# Sheet1.net
KiCad netlist of a schematic drawn in Altium Designer
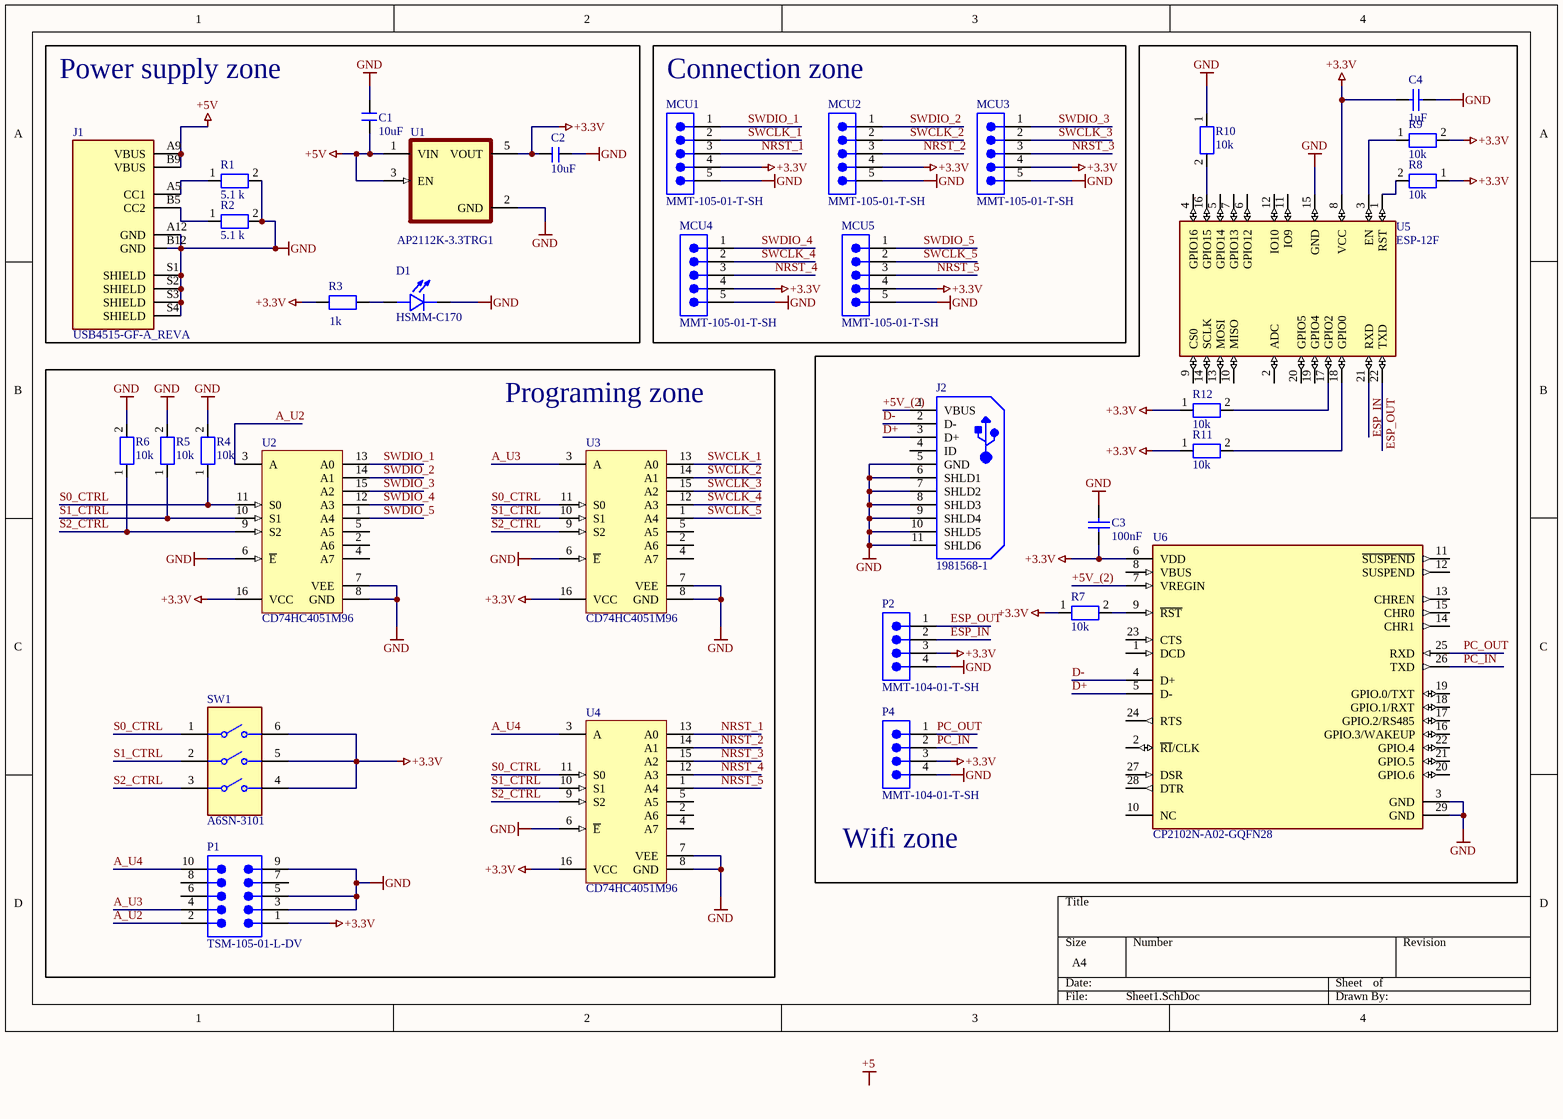
[diagram p0: Sheet1.SchDoc]

(export (version "E")
  (design (tool "Eeschema 10.0.6"))
  (components
    (comp (ref "C1")
      (value "10uF")
      (footprint "CAPC2012X145N")
      (description "10 ÂµF Â±10% 25V Ceramic Capacitor X5R 0805 (2012 Metric)")
      (fields (field (name "MF") "Samsung") (field (name "MP") "CL21A106KAYNNNE"))
      (libsource (lib "CL21A106KAYNNNE") (part "CL21A106KAYNNNE"))
    )
    (comp (ref "C2")
      (value "10uF")
      (footprint "CAPC2012X145N")
      (description "10 ÂµF Â±10% 25V Ceramic Capacitor X5R 0805 (2012 Metric)")
      (fields (field (name "MF") "Samsung") (field (name "MP") "CL21A106KAYNNNE"))
      (libsource (lib "CL21A106KAYNNNE") (part "CL21A106KAYNNNE"))
    )
    (comp (ref "C3")
      (value "100nF")
      (footprint "CAPC2013X135X50LL15T20")
      (fields (field (name "MANUFACTURER") "Vitramon") (field (name "PART NUMBER") "VJ0805Y104KXJCW1BC"))
      (libsource (lib "Altium Content Vault") (part "CAP"))
    )
    (comp (ref "C4")
      (value "1uF")
      (footprint "CAPC2013X140X50NL20T25")
      (fields
        (field (name "PART NUMBER") "0805YD105MAT2A")
        (field (name "MANUFACTURER") "AVX Interconnect / Elco")
      )
      (libsource (lib "Altium Content Vault") (part "CAP"))
    )
    (comp (ref "D1")
      (value "HSMM-C170")
      (footprint "LED_HSMM-C170")
      (libsource (lib "HSMM-C170") (part "HSMM-C170"))
    )
    (comp (ref "J1")
      (value "USB4515-GF-A_REVA")
      (footprint "GCT_USB4515-GF-A_REVA")
      (description "Type C USB Charging Connector")
      (fields
        (field (name "MF") "Global Connector Technology")
        (field (name "DIGI-KEY_PART_NUMBER") "2073-USB4515-GF-ATR-ND")
      )
      (libsource (lib "USB4515-GF-A_REVA") (part "USB4515-GF-A_REVA"))
    )
    (comp (ref "J2")
      (value "1981568-1")
      (footprint "TECO-1981568-5_V")
      (description "Micro USB Receptacle Standard Type B Assy, 5-Pin SMD, RoHS, Tape and Reel")
      (fields (field (name "MANUFACTURER") "TE Connectivity"))
      (libsource (lib "Altium Content Vault") (part "USB-5-6SHLD"))
    )
    (comp (ref "MCU1")
      (value "MMT-105-01-T-SH")
      (footprint "SMTC-MMT-105-01-X-SH")
      (description "Horizontal Surface Mount Header, -55 to 105 degC, 2 mm Pitch, 5-Pin, Male, RoHS")
      (fields (field (name "MANUFACTURER") "Samtec"))
      (libsource (lib "Altium Content Vault") (part "SMTC-MMT-105-01-X-SH"))
    )
    (comp (ref "MCU2")
      (value "MMT-105-01-T-SH")
      (footprint "SMTC-MMT-105-01-X-SH")
      (description "Horizontal Surface Mount Header, -55 to 105 degC, 2 mm Pitch, 5-Pin, Male, RoHS")
      (fields (field (name "MANUFACTURER") "Samtec"))
      (libsource (lib "Altium Content Vault") (part "SMTC-MMT-105-01-X-SH"))
    )
    (comp (ref "MCU3")
      (value "MMT-105-01-T-SH")
      (footprint "SMTC-MMT-105-01-X-SH")
      (description "Horizontal Surface Mount Header, -55 to 105 degC, 2 mm Pitch, 5-Pin, Male, RoHS")
      (fields (field (name "MANUFACTURER") "Samtec"))
      (libsource (lib "Altium Content Vault") (part "SMTC-MMT-105-01-X-SH"))
    )
    (comp (ref "MCU4")
      (value "MMT-105-01-T-SH")
      (footprint "SMTC-MMT-105-01-X-SH")
      (description "Horizontal Surface Mount Header, -55 to 105 degC, 2 mm Pitch, 5-Pin, Male, RoHS")
      (fields (field (name "MANUFACTURER") "Samtec"))
      (libsource (lib "Altium Content Vault") (part "SMTC-MMT-105-01-X-SH"))
    )
    (comp (ref "MCU5")
      (value "MMT-105-01-T-SH")
      (footprint "SMTC-MMT-105-01-X-SH")
      (description "Horizontal Surface Mount Header, -55 to 105 degC, 2 mm Pitch, 5-Pin, Male, RoHS")
      (fields (field (name "MANUFACTURER") "Samtec"))
      (libsource (lib "Altium Content Vault") (part "SMTC-MMT-105-01-X-SH"))
    )
    (comp (ref "P1")
      (value "TSM-105-01-L-DV")
      (footprint "SMTC-TSM-105-01-X-DV")
      (fields (field (name "MANUFACTURER") "Samtec"))
      (libsource (lib "Altium Content Vault") (part "SMTC-TSM-105-01-X-X"))
    )
    (comp (ref "P2")
      (value "MMT-104-01-T-SH")
      (footprint "SMTC-MMT-104-01-X-SH")
      (description "Horizontal Surface Mount Header, -55 to 105 degC, 2 mm Pitch, 4-Pin, Male, RoHS")
      (fields (field (name "MANUFACTURER") "Samtec"))
      (libsource (lib "Altium Content Vault") (part "SMTC-MMT-104-X-X-SH"))
    )
    (comp (ref "P4")
      (value "MMT-104-01-T-SH")
      (footprint "SMTC-MMT-104-01-X-SH")
      (description "Horizontal Surface Mount Header, -55 to 105 degC, 2 mm Pitch, 4-Pin, Male, RoHS")
      (fields (field (name "MANUFACTURER") "Samtec"))
      (libsource (lib "Altium Content Vault") (part "SMTC-MMT-104-X-X-SH"))
    )
    (comp (ref "R1")
      (value "5.1 k")
      (footprint "FP-KTR10-IPC_B")
      (description "Res Thick Film 0805 5.1kΩ 1% 0.125W ±100ppm/°C Automotive Paper T/R")
      (fields (field (name "TOLERANCE") "1%"))
      (libsource (lib "Rez5.1") (part "CMP-08839-031572-1"))
    )
    (comp (ref "R2")
      (value "5.1 k")
      (footprint "FP-KTR10-IPC_B")
      (description "Res Thick Film 0805 5.1kΩ 1% 0.125W ±100ppm/°C Automotive Paper T/R")
      (fields (field (name "TOLERANCE") "1%"))
      (libsource (lib "Rez5.1") (part "CMP-08839-031572-1"))
    )
    (comp (ref "R3")
      (value "1k")
      (footprint "RESC2012X60N")
      (fields (field (name "MP") "CRS0805-JX-102ELF") (field (name "MF") "Bourns"))
      (libsource (lib "1Kohm_rez") (part "CRS0805-JX-102ELF"))
    )
    (comp (ref "R4")
      (value "10k")
      (footprint "FP-CRGP0805-IPC_A")
      (description "CRGP 0805 10K 1%")
      (fields (field (name "MANUFACTURER PART NUMBER") "CRGP0805F10K") (field (name "MANUFACTURER") "TE"))
      (libsource (lib "Rez_5.1K_0805") (part "CMP-03211-006861-1"))
    )
    (comp (ref "R5")
      (value "10k")
      (footprint "FP-CRGP0805-IPC_A")
      (description "CRGP 0805 10K 1%")
      (fields (field (name "MANUFACTURER PART NUMBER") "CRGP0805F10K") (field (name "MANUFACTURER") "TE"))
      (libsource (lib "Rez_5.1K_0805") (part "CMP-03211-006861-1"))
    )
    (comp (ref "R6")
      (value "10k")
      (footprint "FP-CRGP0805-IPC_A")
      (description "CRGP 0805 10K 1%")
      (fields (field (name "MANUFACTURER PART NUMBER") "CRGP0805F10K") (field (name "MANUFACTURER") "TE"))
      (libsource (lib "Rez_5.1K_0805") (part "CMP-03211-006861-1"))
    )
    (comp (ref "R7")
      (value "10k")
      (footprint "FP-CRGP0805-IPC_A")
      (description "CRGP 0805 10K 1%")
      (fields (field (name "MANUFACTURER PART NUMBER") "CRGP0805F10K") (field (name "MANUFACTURER") "TE"))
      (libsource (lib "Rez_5.1K_0805") (part "CMP-03211-006861-1"))
    )
    (comp (ref "R8")
      (value "10k")
      (footprint "FP-CRGP0805-IPC_A")
      (description "CRGP 0805 10K 1%")
      (fields (field (name "MANUFACTURER PART NUMBER") "CRGP0805F10K") (field (name "MANUFACTURER") "TE"))
      (libsource (lib "Rez_5.1K_0805") (part "CMP-03211-006861-1"))
    )
    (comp (ref "R9")
      (value "10k")
      (footprint "FP-CRGP0805-IPC_A")
      (description "CRGP 0805 10K 1%")
      (fields (field (name "MANUFACTURER PART NUMBER") "CRGP0805F10K") (field (name "MANUFACTURER") "TE"))
      (libsource (lib "Rez_5.1K_0805") (part "CMP-03211-006861-1"))
    )
    (comp (ref "R10")
      (value "10k")
      (footprint "FP-CRGP0805-IPC_A")
      (description "CRGP 0805 10K 1%")
      (fields (field (name "MANUFACTURER PART NUMBER") "CRGP0805F10K") (field (name "MANUFACTURER") "TE"))
      (libsource (lib "Rez_5.1K_0805") (part "CMP-03211-006861-1"))
    )
    (comp (ref "R11")
      (value "10k")
      (footprint "FP-CRGP0805-IPC_A")
      (description "CRGP 0805 10K 1%")
      (fields (field (name "MANUFACTURER PART NUMBER") "CRGP0805F10K") (field (name "MANUFACTURER") "TE"))
      (libsource (lib "Rez_5.1K_0805") (part "CMP-03211-006861-1"))
    )
    (comp (ref "R12")
      (value "10k")
      (footprint "FP-CRGP0805-IPC_A")
      (description "CRGP 0805 10K 1%")
      (fields (field (name "MANUFACTURER PART NUMBER") "CRGP0805F10K") (field (name "MANUFACTURER") "TE"))
      (libsource (lib "Rez_5.1K_0805") (part "CMP-03211-006861-1"))
    )
    (comp (ref "SW1")
      (value "A6SN-3101")
      (footprint "FP-A6SN-3101-MFG")
      (description "SWITCH SLIDE DIP SPST 25MA 24V")
      (fields
        (field (name "MANUFACTURER") "Omron Electronics Inc-EMC Div")
        (field (name "OCTOPART") "https://octopart.com/a6sn-3101-omron-55396000")
      )
      (libsource (lib "Altium Content Vault") (part "c5ed29025a0a80be921a75429a93ff4"))
    )
    (comp (ref "U1")
      (value "AP2112K-3.3TRG1")
      (footprint "SOT95P285X140-5N")
      (description "Linear Voltage Regulator IC Positive Fixed 1 Output 600mA SOT-25")
      (fields (field (name "MF") "Diodes Inc."))
      (libsource (lib "AP2112K-3.3TRG1") (part "AP2112K-3.3TRG1"))
    )
    (comp (ref "U2")
      (value "CD74HC4051M96")
      (footprint "D0016A_M")
      (description "High Speed CMOS 8-Channel Analog Multiplexer/Demultiplexer, D0016A, LARGE T&R")
      (fields
        (field (name "GENERIC PART NUMBER") "CD74HC4051")
        (field (name "MANUFACTURER") "Texas Instruments")
      )
      (libsource (lib "Altium Content Vault") (part "TI-CD74HCX4051-16"))
    )
    (comp (ref "U3")
      (value "CD74HC4051M96")
      (footprint "D0016A_M")
      (description "High Speed CMOS 8-Channel Analog Multiplexer/Demultiplexer, D0016A, LARGE T&R")
      (fields
        (field (name "GENERIC PART NUMBER") "CD74HC4051")
        (field (name "MANUFACTURER") "Texas Instruments")
      )
      (libsource (lib "Altium Content Vault") (part "TI-CD74HCX4051-16"))
    )
    (comp (ref "U4")
      (value "CD74HC4051M96")
      (footprint "D0016A_M")
      (description "High Speed CMOS 8-Channel Analog Multiplexer/Demultiplexer, D0016A, LARGE T&R")
      (fields
        (field (name "GENERIC PART NUMBER") "CD74HC4051")
        (field (name "MANUFACTURER") "Texas Instruments")
      )
      (libsource (lib "Altium Content Vault") (part "TI-CD74HCX4051-16"))
    )
    (comp (ref "U5")
      (value "ESP-12F")
      (footprint "ESP-12F")
      (description "WiFi Module")
      (fields (field (name "MF") "AI-Thinker"))
      (libsource (lib "ESP-12F") (part "ESP-12F"))
    )
    (comp (ref "U6")
      (value "CP2102N-A02-GQFN28")
      (footprint "FP-CP2102N-A02-GQFN28-MFG")
      (description "IC USB TO UART BRIDGE QFN28")
      (libsource (lib "Altium Content Vault") (part "f8fb43f618a03b32512863a7a8093b6"))
    )
  )
  (nets
    (net (code "1") (name "+3.3V") (class "Default")
      (node (ref "C2") (pin "1") (pinfunction "1_1") (pintype "passive"))
      (node (ref "C3") (pin "1") (pinfunction "1_1") (pintype "passive"))
      (node (ref "C4") (pin "2") (pinfunction "2_2") (pintype "passive"))
      (node (ref "MCU1") (pin "4") (pinfunction "4_4") (pintype "passive"))
      (node (ref "MCU2") (pin "4") (pinfunction "4_4") (pintype "passive"))
      (node (ref "MCU3") (pin "4") (pinfunction "4_4") (pintype "passive"))
      (node (ref "MCU4") (pin "4") (pinfunction "4_4") (pintype "passive"))
      (node (ref "MCU5") (pin "4") (pinfunction "4_4") (pintype "passive"))
      (node (ref "P1") (pin "1") (pinfunction "1_1") (pintype "passive"))
      (node (ref "P2") (pin "3") (pinfunction "3_3") (pintype "passive"))
      (node (ref "P4") (pin "3") (pinfunction "3_3") (pintype "passive"))
      (node (ref "R11") (pin "1") (pinfunction "1_1") (pintype "passive"))
      (node (ref "R12") (pin "1") (pinfunction "1_1") (pintype "passive"))
      (node (ref "R3") (pin "1") (pinfunction "1_1") (pintype "passive"))
      (node (ref "R7") (pin "1") (pinfunction "1_1") (pintype "passive"))
      (node (ref "R8") (pin "1") (pinfunction "1_1") (pintype "passive"))
      (node (ref "R9") (pin "2") (pinfunction "2_2") (pintype "passive"))
      (node (ref "SW1") (pin "4") (pinfunction "4_4") (pintype "passive"))
      (node (ref "SW1") (pin "5") (pinfunction "5_5") (pintype "passive"))
      (node (ref "SW1") (pin "6") (pinfunction "6_6") (pintype "passive"))
      (node (ref "U1") (pin "5") (pinfunction "VOUT_5") (pintype "power_in"))
      (node (ref "U2") (pin "16") (pinfunction "VCC_16") (pintype "power_in"))
      (node (ref "U3") (pin "16") (pinfunction "VCC_16") (pintype "power_in"))
      (node (ref "U4") (pin "16") (pinfunction "VCC_16") (pintype "power_in"))
      (node (ref "U5") (pin "8") (pinfunction "VCC_8") (pintype "bidirectional"))
      (node (ref "U6") (pin "6") (pinfunction "VDD_6") (pintype "power_in"))
    )
    (net (code "3") (name "+5V") (class "Default")
      (node (ref "C1") (pin "2") (pinfunction "2_2") (pintype "passive"))
      (node (ref "J1") (pin "A9") (pinfunction "VBUS_A9") (pintype "power_in"))
      (node (ref "J1") (pin "B9") (pinfunction "VBUS_B9") (pintype "power_in"))
      (node (ref "U1") (pin "1") (pinfunction "VIN_1") (pintype "power_in"))
      (node (ref "U1") (pin "3") (pinfunction "EN_3") (pintype "input"))
    )
    (net (code "4") (name "/+5V_(2)") (class "Default")
      (node (ref "J2") (pin "1") (pinfunction "VBUS_1") (pintype "passive"))
      (node (ref "U6") (pin "7") (pinfunction "VREGIN_7") (pintype "input"))
    )
    (net (code "5") (name "/A_U2") (class "Default")
      (node (ref "P1") (pin "2") (pinfunction "2_2") (pintype "passive"))
      (node (ref "U2") (pin "3") (pinfunction "A_3") (pintype "passive"))
    )
    (net (code "6") (name "/A_U3") (class "Default")
      (node (ref "P1") (pin "4") (pinfunction "4_4") (pintype "passive"))
      (node (ref "U3") (pin "3") (pinfunction "A_3") (pintype "passive"))
    )
    (net (code "7") (name "/A_U4") (class "Default")
      (node (ref "P1") (pin "10") (pinfunction "10_10") (pintype "passive"))
      (node (ref "U4") (pin "3") (pinfunction "A_3") (pintype "passive"))
    )
    (net (code "8") (name "/D+") (class "Default")
      (node (ref "J2") (pin "3") (pinfunction "D+_3") (pintype "passive"))
      (node (ref "U6") (pin "5") (pinfunction "D-_5") (pintype "passive"))
    )
    (net (code "9") (name "/D-") (class "Default")
      (node (ref "J2") (pin "2") (pinfunction "D-_2") (pintype "passive"))
      (node (ref "U6") (pin "4") (pinfunction "D+_4") (pintype "passive"))
    )
    (net (code "10") (name "/ESP_IN") (class "Default")
      (node (ref "P2") (pin "2") (pinfunction "2_2") (pintype "passive"))
      (node (ref "U5") (pin "21") (pinfunction "RXD_21") (pintype "bidirectional"))
    )
    (net (code "11") (name "/ESP_OUT") (class "Default")
      (node (ref "P2") (pin "1") (pinfunction "1_1") (pintype "passive"))
      (node (ref "U5") (pin "22") (pinfunction "TXD_22") (pintype "bidirectional"))
    )
    (net (code "12") (name "/NRST_1") (class "Default")
      (node (ref "MCU1") (pin "3") (pinfunction "3_3") (pintype "passive"))
      (node (ref "U4") (pin "13") (pinfunction "A0_13") (pintype "passive"))
    )
    (net (code "13") (name "/NRST_2") (class "Default")
      (node (ref "MCU2") (pin "3") (pinfunction "3_3") (pintype "passive"))
      (node (ref "U4") (pin "14") (pinfunction "A1_14") (pintype "passive"))
    )
    (net (code "14") (name "/NRST_3") (class "Default")
      (node (ref "MCU3") (pin "3") (pinfunction "3_3") (pintype "passive"))
      (node (ref "U4") (pin "15") (pinfunction "A2_15") (pintype "passive"))
    )
    (net (code "15") (name "/NRST_4") (class "Default")
      (node (ref "MCU4") (pin "3") (pinfunction "3_3") (pintype "passive"))
      (node (ref "U4") (pin "12") (pinfunction "A3_12") (pintype "passive"))
    )
    (net (code "16") (name "/NRST_5") (class "Default")
      (node (ref "MCU5") (pin "3") (pinfunction "3_3") (pintype "passive"))
      (node (ref "U4") (pin "1") (pinfunction "A4_1") (pintype "passive"))
    )
    (net (code "17") (name "/PC_IN") (class "Default")
      (node (ref "P4") (pin "2") (pinfunction "2_2") (pintype "passive"))
      (node (ref "U6") (pin "26") (pinfunction "TXD_26") (pintype "output"))
    )
    (net (code "18") (name "/PC_OUT") (class "Default")
      (node (ref "P4") (pin "1") (pinfunction "1_1") (pintype "passive"))
      (node (ref "U6") (pin "25") (pinfunction "RXD_25") (pintype "input"))
    )
    (net (code "19") (name "/S0_CTRL") (class "Default")
      (node (ref "R4") (pin "1") (pinfunction "1_1") (pintype "passive"))
      (node (ref "SW1") (pin "1") (pinfunction "1_1") (pintype "passive"))
      (node (ref "U2") (pin "11") (pinfunction "S0_11") (pintype "input"))
      (node (ref "U3") (pin "11") (pinfunction "S0_11") (pintype "input"))
      (node (ref "U4") (pin "11") (pinfunction "S0_11") (pintype "input"))
    )
    (net (code "20") (name "/S1_CTRL") (class "Default")
      (node (ref "R5") (pin "1") (pinfunction "1_1") (pintype "passive"))
      (node (ref "SW1") (pin "2") (pinfunction "2_2") (pintype "passive"))
      (node (ref "U2") (pin "10") (pinfunction "S1_10") (pintype "input"))
      (node (ref "U3") (pin "10") (pinfunction "S1_10") (pintype "input"))
      (node (ref "U4") (pin "10") (pinfunction "S1_10") (pintype "input"))
    )
    (net (code "21") (name "/S2_CTRL") (class "Default")
      (node (ref "R6") (pin "1") (pinfunction "1_1") (pintype "passive"))
      (node (ref "SW1") (pin "3") (pinfunction "3_3") (pintype "passive"))
      (node (ref "U2") (pin "9") (pinfunction "S2_9") (pintype "input"))
      (node (ref "U3") (pin "9") (pinfunction "S2_9") (pintype "input"))
      (node (ref "U4") (pin "9") (pinfunction "S2_9") (pintype "input"))
    )
    (net (code "22") (name "/SWCLK_1") (class "Default")
      (node (ref "MCU1") (pin "2") (pinfunction "2_2") (pintype "passive"))
      (node (ref "U3") (pin "13") (pinfunction "A0_13") (pintype "passive"))
    )
    (net (code "23") (name "/SWCLK_2") (class "Default")
      (node (ref "MCU2") (pin "2") (pinfunction "2_2") (pintype "passive"))
      (node (ref "U3") (pin "14") (pinfunction "A1_14") (pintype "passive"))
    )
    (net (code "24") (name "/SWCLK_3") (class "Default")
      (node (ref "MCU3") (pin "2") (pinfunction "2_2") (pintype "passive"))
      (node (ref "U3") (pin "15") (pinfunction "A2_15") (pintype "passive"))
    )
    (net (code "25") (name "/SWCLK_4") (class "Default")
      (node (ref "MCU4") (pin "2") (pinfunction "2_2") (pintype "passive"))
      (node (ref "U3") (pin "12") (pinfunction "A3_12") (pintype "passive"))
    )
    (net (code "26") (name "/SWCLK_5") (class "Default")
      (node (ref "MCU5") (pin "2") (pinfunction "2_2") (pintype "passive"))
      (node (ref "U3") (pin "1") (pinfunction "A4_1") (pintype "passive"))
    )
    (net (code "27") (name "/SWDIO_1") (class "Default")
      (node (ref "MCU1") (pin "1") (pinfunction "1_1") (pintype "passive"))
      (node (ref "U2") (pin "13") (pinfunction "A0_13") (pintype "passive"))
    )
    (net (code "28") (name "/SWDIO_2") (class "Default")
      (node (ref "MCU2") (pin "1") (pinfunction "1_1") (pintype "passive"))
      (node (ref "U2") (pin "14") (pinfunction "A1_14") (pintype "passive"))
    )
    (net (code "29") (name "/SWDIO_3") (class "Default")
      (node (ref "MCU3") (pin "1") (pinfunction "1_1") (pintype "passive"))
      (node (ref "U2") (pin "15") (pinfunction "A2_15") (pintype "passive"))
    )
    (net (code "30") (name "/SWDIO_4") (class "Default")
      (node (ref "MCU4") (pin "1") (pinfunction "1_1") (pintype "passive"))
      (node (ref "U2") (pin "12") (pinfunction "A3_12") (pintype "passive"))
    )
    (net (code "31") (name "/SWDIO_5") (class "Default")
      (node (ref "MCU5") (pin "1") (pinfunction "1_1") (pintype "passive"))
      (node (ref "U2") (pin "1") (pinfunction "A4_1") (pintype "passive"))
    )
    (net (code "32") (name "GND") (class "Default")
      (node (ref "C1") (pin "1") (pinfunction "1_1") (pintype "passive"))
      (node (ref "C2") (pin "2") (pinfunction "2_2") (pintype "passive"))
      (node (ref "C3") (pin "2") (pinfunction "2_2") (pintype "passive"))
      (node (ref "C4") (pin "1") (pinfunction "1_1") (pintype "passive"))
      (node (ref "D1") (pin "C") (pinfunction "C_C") (pintype "passive"))
      (node (ref "J1") (pin "A12") (pinfunction "GND_A12") (pintype "power_in"))
      (node (ref "J1") (pin "B12") (pinfunction "GND_B12") (pintype "power_in"))
      (node (ref "J1") (pin "S1") (pinfunction "SHIELD_S1") (pintype "power_in"))
      (node (ref "J1") (pin "S2") (pinfunction "SHIELD_S2") (pintype "power_in"))
      (node (ref "J1") (pin "S3") (pinfunction "SHIELD_S3") (pintype "power_in"))
      (node (ref "J1") (pin "S4") (pinfunction "SHIELD_S4") (pintype "power_in"))
      (node (ref "J2") (pin "10") (pinfunction "SHLD5_10") (pintype "passive"))
      (node (ref "J2") (pin "11") (pinfunction "SHLD6_11") (pintype "passive"))
      (node (ref "J2") (pin "5") (pinfunction "GND_5") (pintype "passive"))
      (node (ref "J2") (pin "6") (pinfunction "SHLD1_6") (pintype "passive"))
      (node (ref "J2") (pin "7") (pinfunction "SHLD2_7") (pintype "passive"))
      (node (ref "J2") (pin "8") (pinfunction "SHLD3_8") (pintype "passive"))
      (node (ref "J2") (pin "9") (pinfunction "SHLD4_9") (pintype "passive"))
      (node (ref "MCU1") (pin "5") (pinfunction "5_5") (pintype "passive"))
      (node (ref "MCU2") (pin "5") (pinfunction "5_5") (pintype "passive"))
      (node (ref "MCU3") (pin "5") (pinfunction "5_5") (pintype "passive"))
      (node (ref "MCU4") (pin "5") (pinfunction "5_5") (pintype "passive"))
      (node (ref "MCU5") (pin "5") (pinfunction "5_5") (pintype "passive"))
      (node (ref "P1") (pin "3") (pinfunction "3_3") (pintype "passive"))
      (node (ref "P1") (pin "5") (pinfunction "5_5") (pintype "passive"))
      (node (ref "P1") (pin "9") (pinfunction "9_9") (pintype "passive"))
      (node (ref "P2") (pin "4") (pinfunction "4_4") (pintype "passive"))
      (node (ref "P4") (pin "4") (pinfunction "4_4") (pintype "passive"))
      (node (ref "R1") (pin "2") (pinfunction "2_2") (pintype "passive"))
      (node (ref "R10") (pin "1") (pinfunction "1_1") (pintype "passive"))
      (node (ref "R2") (pin "2") (pinfunction "2_2") (pintype "passive"))
      (node (ref "R4") (pin "2") (pinfunction "2_2") (pintype "passive"))
      (node (ref "R5") (pin "2") (pinfunction "2_2") (pintype "passive"))
      (node (ref "R6") (pin "2") (pinfunction "2_2") (pintype "passive"))
      (node (ref "U1") (pin "2") (pinfunction "GND_2") (pintype "power_in"))
      (node (ref "U2") (pin "6") (pinfunction "~{E}_6") (pintype "input"))
      (node (ref "U2") (pin "7") (pinfunction "VEE_7") (pintype "power_in"))
      (node (ref "U2") (pin "8") (pinfunction "GND_8") (pintype "power_in"))
      (node (ref "U3") (pin "6") (pinfunction "~{E}_6") (pintype "input"))
      (node (ref "U3") (pin "7") (pinfunction "VEE_7") (pintype "power_in"))
      (node (ref "U3") (pin "8") (pinfunction "GND_8") (pintype "power_in"))
      (node (ref "U4") (pin "6") (pinfunction "~{E}_6") (pintype "input"))
      (node (ref "U4") (pin "7") (pinfunction "VEE_7") (pintype "power_in"))
      (node (ref "U4") (pin "8") (pinfunction "GND_8") (pintype "power_in"))
      (node (ref "U5") (pin "15") (pinfunction "GND_15") (pintype "bidirectional"))
      (node (ref "U6") (pin "29") (pinfunction "GND_29") (pintype "power_in"))
      (node (ref "U6") (pin "3") (pinfunction "GND_3") (pintype "power_in"))
    )
    (net (code "33") (name "Net-(D1-PadA)") (class "Default")
      (node (ref "D1") (pin "A") (pinfunction "A_A") (pintype "passive"))
      (node (ref "R3") (pin "2") (pinfunction "2_2") (pintype "passive"))
    )
    (net (code "34") (name "Net-(J1-CC1)") (class "Default")
      (node (ref "J1") (pin "A5") (pinfunction "CC1_A5") (pintype "passive"))
      (node (ref "R1") (pin "1") (pinfunction "1_1") (pintype "passive"))
    )
    (net (code "35") (name "Net-(J1-CC2)") (class "Default")
      (node (ref "J1") (pin "B5") (pinfunction "CC2_B5") (pintype "passive"))
      (node (ref "R2") (pin "1") (pinfunction "1_1") (pintype "passive"))
    )
    (net (code "36") (name "Net-(U5-EN)") (class "Default")
      (node (ref "R9") (pin "1") (pinfunction "1_1") (pintype "passive"))
      (node (ref "U5") (pin "3") (pinfunction "EN_3") (pintype "bidirectional"))
    )
    (net (code "37") (name "Net-(U5-GPIO0)") (class "Default")
      (node (ref "R11") (pin "2") (pinfunction "2_2") (pintype "passive"))
      (node (ref "U5") (pin "18") (pinfunction "GPIO0_18") (pintype "bidirectional"))
    )
    (net (code "38") (name "Net-(U5-GPIO2)") (class "Default")
      (node (ref "R12") (pin "2") (pinfunction "2_2") (pintype "passive"))
      (node (ref "U5") (pin "17") (pinfunction "GPIO2_17") (pintype "bidirectional"))
    )
    (net (code "39") (name "Net-(U5-GPIO15)") (class "Default")
      (node (ref "R10") (pin "2") (pinfunction "2_2") (pintype "passive"))
      (node (ref "U5") (pin "16") (pinfunction "GPIO15_16") (pintype "bidirectional"))
    )
    (net (code "40") (name "Net-(U5-RST)") (class "Default")
      (node (ref "R8") (pin "2") (pinfunction "2_2") (pintype "passive"))
      (node (ref "U5") (pin "1") (pinfunction "RST_1") (pintype "bidirectional"))
    )
    (net (code "41") (name "Net-(U6-~{RST})") (class "Default")
      (node (ref "R7") (pin "2") (pinfunction "2_2") (pintype "passive"))
      (node (ref "U6") (pin "9") (pinfunction "~{RST}_9") (pintype "input"))
    )
    (net (code "42") (name "unconnected-(J2-ID-Pad4)") (class "Default")
      (node (ref "J2") (pin "4") (pinfunction "ID_4") (pintype "passive"))
    )
    (net (code "43") (name "unconnected-(P1-Pad6)") (class "Default")
      (node (ref "P1") (pin "6") (pinfunction "6_6") (pintype "passive"))
    )
    (net (code "44") (name "unconnected-(P1-Pad7)") (class "Default")
      (node (ref "P1") (pin "7") (pinfunction "7_7") (pintype "passive"))
    )
    (net (code "45") (name "unconnected-(P1-Pad8)") (class "Default")
      (node (ref "P1") (pin "8") (pinfunction "8_8") (pintype "passive"))
    )
    (net (code "46") (name "unconnected-(U2-A5-Pad5)") (class "Default")
      (node (ref "U2") (pin "5") (pinfunction "A5_5") (pintype "passive"))
    )
    (net (code "47") (name "unconnected-(U2-A6-Pad2)") (class "Default")
      (node (ref "U2") (pin "2") (pinfunction "A6_2") (pintype "passive"))
    )
    (net (code "48") (name "unconnected-(U2-A7-Pad4)") (class "Default")
      (node (ref "U2") (pin "4") (pinfunction "A7_4") (pintype "passive"))
    )
    (net (code "49") (name "unconnected-(U3-A5-Pad5)") (class "Default")
      (node (ref "U3") (pin "5") (pinfunction "A5_5") (pintype "passive"))
    )
    (net (code "50") (name "unconnected-(U3-A6-Pad2)") (class "Default")
      (node (ref "U3") (pin "2") (pinfunction "A6_2") (pintype "passive"))
    )
    (net (code "51") (name "unconnected-(U3-A7-Pad4)") (class "Default")
      (node (ref "U3") (pin "4") (pinfunction "A7_4") (pintype "passive"))
    )
    (net (code "52") (name "unconnected-(U4-A5-Pad5)") (class "Default")
      (node (ref "U4") (pin "5") (pinfunction "A5_5") (pintype "passive"))
    )
    (net (code "53") (name "unconnected-(U4-A6-Pad2)") (class "Default")
      (node (ref "U4") (pin "2") (pinfunction "A6_2") (pintype "passive"))
    )
    (net (code "54") (name "unconnected-(U4-A7-Pad4)") (class "Default")
      (node (ref "U4") (pin "4") (pinfunction "A7_4") (pintype "passive"))
    )
    (net (code "55") (name "unconnected-(U5-ADC-Pad2)") (class "Default")
      (node (ref "U5") (pin "2") (pinfunction "ADC_2") (pintype "bidirectional"))
    )
    (net (code "56") (name "unconnected-(U5-CS0-Pad9)") (class "Default")
      (node (ref "U5") (pin "9") (pinfunction "CS0_9") (pintype "bidirectional"))
    )
    (net (code "57") (name "unconnected-(U5-GPIO4-Pad19)") (class "Default")
      (node (ref "U5") (pin "19") (pinfunction "GPIO4_19") (pintype "bidirectional"))
    )
    (net (code "58") (name "unconnected-(U5-GPIO5-Pad20)") (class "Default")
      (node (ref "U5") (pin "20") (pinfunction "GPIO5_20") (pintype "bidirectional"))
    )
    (net (code "59") (name "unconnected-(U5-GPIO12-Pad6)") (class "Default")
      (node (ref "U5") (pin "6") (pinfunction "GPIO12_6") (pintype "bidirectional"))
    )
    (net (code "60") (name "unconnected-(U5-GPIO13-Pad7)") (class "Default")
      (node (ref "U5") (pin "7") (pinfunction "GPIO13_7") (pintype "bidirectional"))
    )
    (net (code "61") (name "unconnected-(U5-GPIO14-Pad5)") (class "Default")
      (node (ref "U5") (pin "5") (pinfunction "GPIO14_5") (pintype "bidirectional"))
    )
    (net (code "62") (name "unconnected-(U5-GPIO16-Pad4)") (class "Default")
      (node (ref "U5") (pin "4") (pinfunction "GPIO16_4") (pintype "bidirectional"))
    )
    (net (code "63") (name "unconnected-(U5-IO9-Pad11)") (class "Default")
      (node (ref "U5") (pin "11") (pinfunction "IO9_11") (pintype "bidirectional"))
    )
    (net (code "64") (name "unconnected-(U5-IO10-Pad12)") (class "Default")
      (node (ref "U5") (pin "12") (pinfunction "IO10_12") (pintype "bidirectional"))
    )
    (net (code "65") (name "unconnected-(U5-MISO-Pad10)") (class "Default")
      (node (ref "U5") (pin "10") (pinfunction "MISO_10") (pintype "bidirectional"))
    )
    (net (code "66") (name "unconnected-(U5-MOSI-Pad13)") (class "Default")
      (node (ref "U5") (pin "13") (pinfunction "MOSI_13") (pintype "bidirectional"))
    )
    (net (code "67") (name "unconnected-(U5-SCLK-Pad14)") (class "Default")
      (node (ref "U5") (pin "14") (pinfunction "SCLK_14") (pintype "bidirectional"))
    )
    (net (code "68") (name "unconnected-(U6-CHR0-Pad15)") (class "Default")
      (node (ref "U6") (pin "15") (pinfunction "CHR0_15") (pintype "output"))
    )
    (net (code "69") (name "unconnected-(U6-CHR1-Pad14)") (class "Default")
      (node (ref "U6") (pin "14") (pinfunction "CHR1_14") (pintype "output"))
    )
    (net (code "70") (name "unconnected-(U6-CHREN-Pad13)") (class "Default")
      (node (ref "U6") (pin "13") (pinfunction "CHREN_13") (pintype "output"))
    )
    (net (code "71") (name "unconnected-(U6-CTS-Pad23)") (class "Default")
      (node (ref "U6") (pin "23") (pinfunction "CTS_23") (pintype "input"))
    )
    (net (code "72") (name "unconnected-(U6-DCD-Pad1)") (class "Default")
      (node (ref "U6") (pin "1") (pinfunction "DCD_1") (pintype "input"))
    )
    (net (code "73") (name "unconnected-(U6-DSR-Pad27)") (class "Default")
      (node (ref "U6") (pin "27") (pinfunction "DSR_27") (pintype "input"))
    )
    (net (code "74") (name "unconnected-(U6-DTR-Pad28)") (class "Default")
      (node (ref "U6") (pin "28") (pinfunction "DTR_28") (pintype "output"))
    )
    (net (code "75") (name "unconnected-(U6-GPIO.0{slash}TXT-Pad19)") (class "Default")
      (node (ref "U6") (pin "19") (pinfunction "GPIO.0/TXT_19") (pintype "bidirectional"))
    )
    (net (code "76") (name "unconnected-(U6-GPIO.1{slash}RXT-Pad18)") (class "Default")
      (node (ref "U6") (pin "18") (pinfunction "GPIO.1/RXT_18") (pintype "bidirectional"))
    )
    (net (code "77") (name "unconnected-(U6-GPIO.2{slash}RS485-Pad17)") (class "Default")
      (node (ref "U6") (pin "17") (pinfunction "GPIO.2/RS485_17") (pintype "bidirectional"))
    )
    (net (code "78") (name "unconnected-(U6-GPIO.3{slash}WAKEUP-Pad16)") (class "Default")
      (node (ref "U6") (pin "16") (pinfunction "GPIO.3/WAKEUP_16") (pintype "bidirectional"))
    )
    (net (code "79") (name "unconnected-(U6-GPIO.4-Pad22)") (class "Default")
      (node (ref "U6") (pin "22") (pinfunction "GPIO.4_22") (pintype "bidirectional"))
    )
    (net (code "80") (name "unconnected-(U6-GPIO.5-Pad21)") (class "Default")
      (node (ref "U6") (pin "21") (pinfunction "GPIO.5_21") (pintype "bidirectional"))
    )
    (net (code "81") (name "unconnected-(U6-GPIO.6-Pad20)") (class "Default")
      (node (ref "U6") (pin "20") (pinfunction "GPIO.6_20") (pintype "bidirectional"))
    )
    (net (code "82") (name "unconnected-(U6-NC-Pad10)") (class "Default")
      (node (ref "U6") (pin "10") (pinfunction "NC_10") (pintype "passive"))
    )
    (net (code "83") (name "unconnected-(U6-RTS-Pad24)") (class "Default")
      (node (ref "U6") (pin "24") (pinfunction "RTS_24") (pintype "output"))
    )
    (net (code "84") (name "unconnected-(U6-SUSPEND-Pad12)") (class "Default")
      (node (ref "U6") (pin "12") (pinfunction "SUSPEND_12") (pintype "output"))
    )
    (net (code "85") (name "unconnected-(U6-VBUS-Pad8)") (class "Default")
      (node (ref "U6") (pin "8") (pinfunction "VBUS_8") (pintype "input"))
    )
    (net (code "86") (name "unconnected-(U6-~{RI}{slash}CLK-Pad2)") (class "Default")
      (node (ref "U6") (pin "2") (pinfunction "~{RI}/CLK_2") (pintype "bidirectional"))
    )
    (net (code "87") (name "unconnected-(U6-~{SUSPEND}-Pad11)") (class "Default")
      (node (ref "U6") (pin "11") (pinfunction "~{SUSPEND}_11") (pintype "output"))
    )
  )
)
